# Test_1.net
KiCad netlist of a schematic drawn in EAGLE
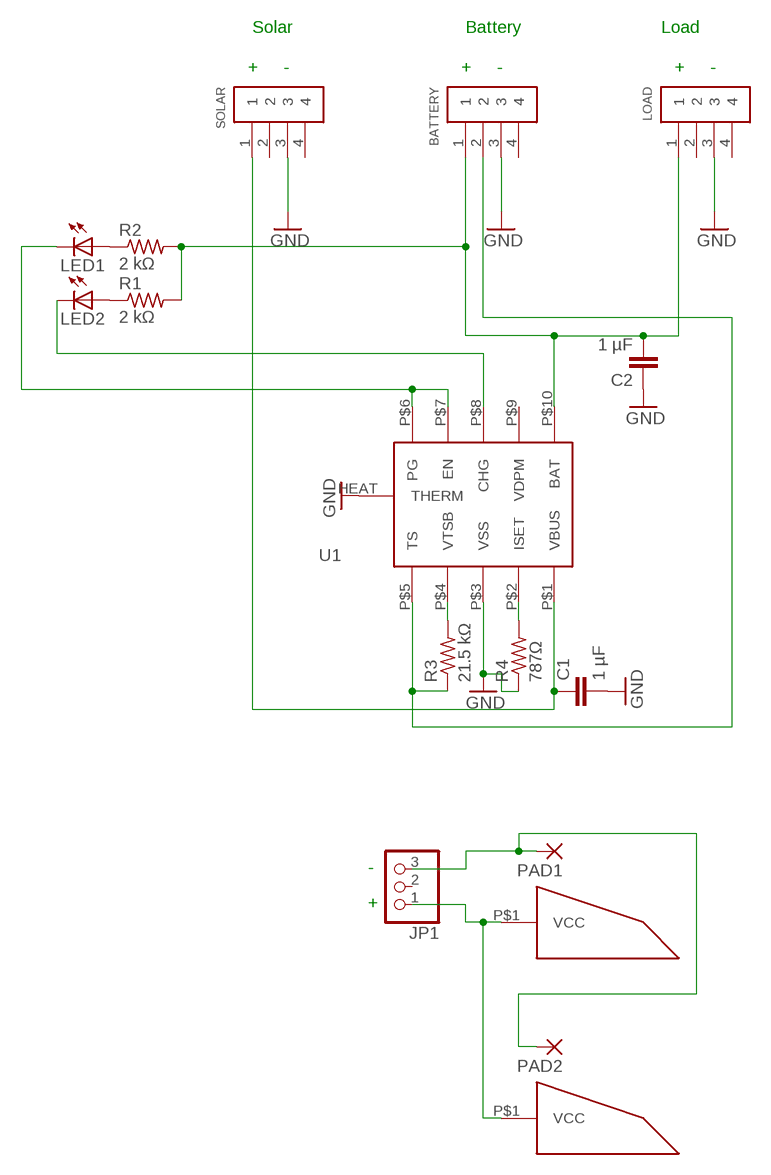
[diagram p0: schematic, sheet 1]

(export (version "E")
  (design (tool "Eeschema 10.0.6"))
  (components
    (comp (ref "BATTERY")
      (value "1X4-CLEANBIG")
      (footprint "eagle-import:1X04-CLEANBIG")
      (libsource (lib "eagle-import") (part "1X4-CLEANBIG"))
    )
    (comp (ref "C1")
      (value "1 µF")
      (footprint "eagle-import:C0805")
      (libsource (lib "eagle-import") (part "C-EUC0805"))
    )
    (comp (ref "C2")
      (value "1 µF")
      (footprint "eagle-import:C0805")
      (libsource (lib "eagle-import") (part "C-EUC0805"))
    )
    (comp (ref "JP1")
      (value "PINHD-1X3")
      (footprint "eagle-import:1X03")
      (libsource (lib "eagle-import") (part "PINHD-1X3"))
    )
    (comp (ref "LED1")
      (value "LEDCHIP-LED0805")
      (footprint "eagle-import:CHIP-LED0805")
      (libsource (lib "eagle-import") (part "LEDCHIP-LED0805"))
    )
    (comp (ref "LED2")
      (value "LEDCHIP-LED0805")
      (footprint "eagle-import:CHIP-LED0805")
      (libsource (lib "eagle-import") (part "LEDCHIP-LED0805"))
    )
    (comp (ref "LOAD")
      (value "1X4-CLEANBIG")
      (footprint "eagle-import:1X04-CLEANBIG")
      (libsource (lib "eagle-import") (part "1X4-CLEANBIG"))
    )
    (comp (ref "PAD1")
      (value "SMD2")
      (footprint "eagle-import:SMD1,27-2,54")
      (libsource (lib "eagle-import") (part "SMD2"))
    )
    (comp (ref "PAD2")
      (value "SMD2")
      (footprint "eagle-import:SMD1,27-2,54")
      (libsource (lib "eagle-import") (part "SMD2"))
    )
    (comp (ref "R1")
      (value "2 kΩ")
      (footprint "eagle-import:R0805")
      (libsource (lib "eagle-import") (part "R-US_R0805"))
    )
    (comp (ref "R2")
      (value "2 kΩ")
      (footprint "eagle-import:R0805")
      (libsource (lib "eagle-import") (part "R-US_R0805"))
    )
    (comp (ref "R3")
      (value "21.5 kΩ")
      (footprint "eagle-import:R0805")
      (libsource (lib "eagle-import") (part "R-US_R0805"))
    )
    (comp (ref "R4")
      (value "787Ω")
      (footprint "eagle-import:R0805")
      (libsource (lib "eagle-import") (part "R-US_R0805"))
    )
    (comp (ref "SOLAR")
      (value "1X4-CLEANBIG")
      (footprint "eagle-import:1X04-CLEANBIG")
      (libsource (lib "eagle-import") (part "1X4-CLEANBIG"))
    )
    (comp (ref "U$1")
      (value "TRISOLX")
      (footprint "eagle-import:TRISOLX")
      (libsource (lib "eagle-import") (part "TRISOLX"))
    )
    (comp (ref "U$2")
      (value "TRISOLX")
      (footprint "eagle-import:TRISOLX")
      (libsource (lib "eagle-import") (part "TRISOLX"))
    )
    (comp (ref "U1")
      (value "BQ24210")
      (footprint "eagle-import:BQ24210")
      (libsource (lib "eagle-import") (part "BQ24210"))
    )
  )
  (nets
    (net (code "1") (name "GND") (class "Default")
      (node (ref "BATTERY") (pin "3") (pinfunction "3_3") (pintype "bidirectional"))
      (node (ref "C1") (pin "2") (pinfunction "2_2") (pintype "passive"))
      (node (ref "C2") (pin "1") (pinfunction "1_1") (pintype "passive"))
      (node (ref "LOAD") (pin "3") (pinfunction "3_3") (pintype "bidirectional"))
      (node (ref "R4") (pin "1") (pinfunction "1_1") (pintype "passive"))
      (node (ref "SOLAR") (pin "3") (pinfunction "3_3") (pintype "bidirectional"))
      (node (ref "U1") (pin "HEAT") (pinfunction "THERM_HEAT") (pintype "power_in"))
      (node (ref "U1") (pin "P$3") (pinfunction "VSS_P$3") (pintype "power_in"))
    )
    (net (code "2") (name "Net-(LED1-PadA)") (class "Default")
      (node (ref "LED1") (pin "A") (pinfunction "A_A") (pintype "passive"))
      (node (ref "R2") (pin "1") (pinfunction "1_1") (pintype "passive"))
    )
    (net (code "3") (name "Net-(LED2-PadA)") (class "Default")
      (node (ref "LED2") (pin "A") (pinfunction "A_A") (pintype "passive"))
      (node (ref "R1") (pin "1") (pinfunction "1_1") (pintype "passive"))
    )
    (net (code "4") (name "Net-(PAD1-P)") (class "Default")
      (node (ref "JP1") (pin "3") (pinfunction "3_3") (pintype "passive"))
      (node (ref "PAD1") (pin "1") (pinfunction "P_1") (pintype "passive"))
      (node (ref "PAD2") (pin "1") (pinfunction "P_1") (pintype "passive"))
    )
    (net (code "5") (name "Net-(U$1-VCC)") (class "Default")
      (node (ref "JP1") (pin "1") (pinfunction "1_1") (pintype "passive"))
      (node (ref "U$1") (pin "P$1") (pinfunction "VCC_P$1") (pintype "power_in"))
      (node (ref "U$2") (pin "P$1") (pinfunction "VCC_P$1") (pintype "power_in"))
    )
    (net (code "6") (name "Net-(U1-BAT)") (class "Default")
      (node (ref "BATTERY") (pin "1") (pinfunction "1_1") (pintype "bidirectional"))
      (node (ref "C2") (pin "2") (pinfunction "2_2") (pintype "passive"))
      (node (ref "LOAD") (pin "1") (pinfunction "1_1") (pintype "bidirectional"))
      (node (ref "R1") (pin "2") (pinfunction "2_2") (pintype "passive"))
      (node (ref "R2") (pin "2") (pinfunction "2_2") (pintype "passive"))
      (node (ref "U1") (pin "P$10") (pinfunction "BAT_P$10") (pintype "bidirectional"))
    )
    (net (code "7") (name "Net-(U1-CHG)") (class "Default")
      (node (ref "LED2") (pin "C") (pinfunction "C_C") (pintype "passive"))
      (node (ref "U1") (pin "P$8") (pinfunction "CHG_P$8") (pintype "output"))
    )
    (net (code "8") (name "Net-(U1-EN)") (class "Default")
      (node (ref "LED1") (pin "C") (pinfunction "C_C") (pintype "passive"))
      (node (ref "U1") (pin "P$6") (pinfunction "PG_P$6") (pintype "output"))
      (node (ref "U1") (pin "P$7") (pinfunction "EN_P$7") (pintype "input"))
    )
    (net (code "9") (name "Net-(U1-ISET)") (class "Default")
      (node (ref "R4") (pin "2") (pinfunction "2_2") (pintype "passive"))
      (node (ref "U1") (pin "P$2") (pinfunction "ISET_P$2") (pintype "input"))
    )
    (net (code "10") (name "Net-(U1-TS)") (class "Default")
      (node (ref "BATTERY") (pin "2") (pinfunction "2_2") (pintype "bidirectional"))
      (node (ref "R3") (pin "1") (pinfunction "1_1") (pintype "passive"))
      (node (ref "U1") (pin "P$5") (pinfunction "TS_P$5") (pintype "input"))
    )
    (net (code "11") (name "Net-(U1-VBUS)") (class "Default")
      (node (ref "C1") (pin "1") (pinfunction "1_1") (pintype "passive"))
      (node (ref "SOLAR") (pin "1") (pinfunction "1_1") (pintype "bidirectional"))
      (node (ref "U1") (pin "P$1") (pinfunction "VBUS_P$1") (pintype "bidirectional"))
    )
    (net (code "12") (name "Net-(U1-VTSB)") (class "Default")
      (node (ref "R3") (pin "2") (pinfunction "2_2") (pintype "passive"))
      (node (ref "U1") (pin "P$4") (pinfunction "VTSB_P$4") (pintype "output"))
    )
    (net (code "13") (name "unconnected-(BATTERY-Pad4)") (class "Default")
      (node (ref "BATTERY") (pin "4") (pinfunction "4_4") (pintype "bidirectional"))
    )
    (net (code "14") (name "unconnected-(JP1-Pad2)") (class "Default")
      (node (ref "JP1") (pin "2") (pinfunction "2_2") (pintype "passive"))
    )
    (net (code "15") (name "unconnected-(LOAD-Pad2)") (class "Default")
      (node (ref "LOAD") (pin "2") (pinfunction "2_2") (pintype "bidirectional"))
    )
    (net (code "16") (name "unconnected-(LOAD-Pad4)") (class "Default")
      (node (ref "LOAD") (pin "4") (pinfunction "4_4") (pintype "bidirectional"))
    )
    (net (code "17") (name "unconnected-(SOLAR-Pad2)") (class "Default")
      (node (ref "SOLAR") (pin "2") (pinfunction "2_2") (pintype "bidirectional"))
    )
    (net (code "18") (name "unconnected-(SOLAR-Pad4)") (class "Default")
      (node (ref "SOLAR") (pin "4") (pinfunction "4_4") (pintype "bidirectional"))
    )
    (net (code "19") (name "unconnected-(U1-VDPM-PadP$9)") (class "Default")
      (node (ref "U1") (pin "P$9") (pinfunction "VDPM_P$9") (pintype "input"))
    )
  )
)
